# V1_0.net
KiCad netlist of a schematic drawn in Altium Designer
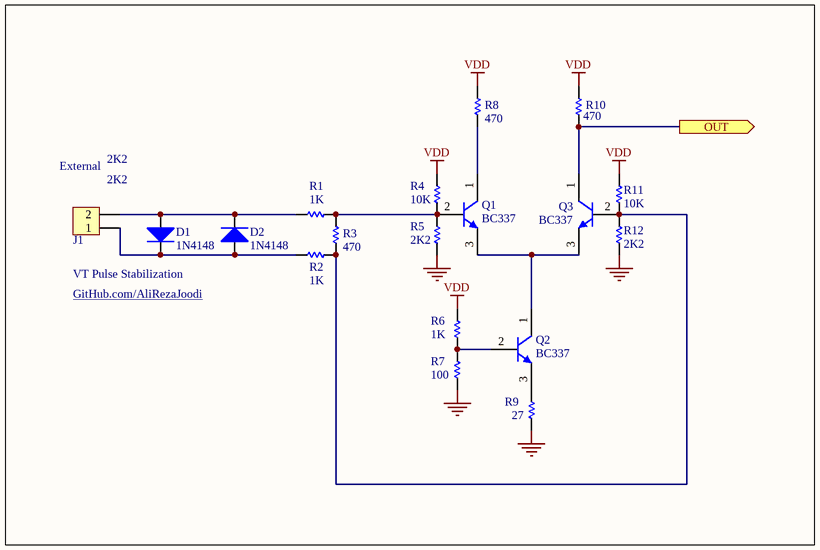
[diagram p0: V1.0.SchDoc]

(export (version "E")
  (design (tool "Eeschema 10.0.6"))
  (components
    (comp (ref "D1")
      (value "1N4148")
      (footprint "D_THD_AXIAL0.3_DO-35")
      (description "Diode,")
      (libsource (lib "Passive") (part "Diode"))
    )
    (comp (ref "D2")
      (value "1N4148")
      (footprint "D_THD_AXIAL0.3_DO-35")
      (description "Diode,")
      (libsource (lib "Passive") (part "Diode"))
    )
    (comp (ref "J1")
      (value "2PIN")
      (footprint "Connector_Phoenix_2PIN_MSTB")
      (description "Connector, Header, 2Pin")
      (libsource (lib "Connector") (part "Connector_Header_2Pin"))
    )
    (comp (ref "Q1")
      (value "BC337")
      (footprint "TO92_3Pin_Form3")
      (description "Transistor, BJT, NPN")
      (libsource (lib "Passive") (part "Transistor_BJT_NPN"))
    )
    (comp (ref "Q2")
      (value "BC337")
      (footprint "TO92_3Pin_Form3")
      (description "Transistor, BJT, NPN")
      (libsource (lib "Passive") (part "Transistor_BJT_NPN"))
    )
    (comp (ref "Q3")
      (value "BC337")
      (footprint "TO92_3Pin_Form3")
      (description "Transistor, BJT, NPN")
      (libsource (lib "Passive") (part "Transistor_BJT_NPN"))
    )
    (comp (ref "R1")
      (value "1K")
      (footprint "R_THD_AXIAL0.4(1/4W)")
      (description "Resistor,")
      (libsource (lib "Passive") (part "Resistor"))
    )
    (comp (ref "R2")
      (value "1K")
      (footprint "R_THD_AXIAL0.4(1/4W)")
      (description "Resistor,")
      (libsource (lib "Passive") (part "Resistor"))
    )
    (comp (ref "R3")
      (value "470")
      (footprint "R_THD_AXIAL0.4(1/4W)")
      (description "Resistor,")
      (libsource (lib "Passive") (part "Resistor"))
    )
    (comp (ref "R4")
      (value "10K")
      (footprint "R_THD_AXIAL0.4(1/4W)")
      (description "Resistor,")
      (libsource (lib "Passive") (part "Resistor"))
    )
    (comp (ref "R5")
      (value "2K2")
      (footprint "R_THD_AXIAL0.4(1/4W)")
      (description "Resistor,")
      (libsource (lib "Passive") (part "Resistor"))
    )
    (comp (ref "R6")
      (value "1K")
      (footprint "R_THD_AXIAL0.4(1/4W)")
      (description "Resistor,")
      (libsource (lib "Passive") (part "Resistor"))
    )
    (comp (ref "R7")
      (value "100")
      (footprint "R_THD_AXIAL0.4(1/4W)")
      (description "Resistor,")
      (libsource (lib "Passive") (part "Resistor"))
    )
    (comp (ref "R8")
      (value "470")
      (footprint "R_THD_AXIAL0.4(1/4W)")
      (description "Resistor,")
      (libsource (lib "Passive") (part "Resistor"))
    )
    (comp (ref "R9")
      (value "27")
      (footprint "R_THD_AXIAL0.4(1/4W)")
      (description "Resistor,")
      (libsource (lib "Passive") (part "Resistor"))
    )
    (comp (ref "R10")
      (value "470")
      (footprint "R_THD_AXIAL0.4(1/4W)")
      (description "Resistor,")
      (libsource (lib "Passive") (part "Resistor"))
    )
    (comp (ref "R11")
      (value "10K")
      (footprint "R_THD_AXIAL0.4(1/4W)")
      (description "Resistor,")
      (libsource (lib "Passive") (part "Resistor"))
    )
    (comp (ref "R12")
      (value "2K2")
      (footprint "R_THD_AXIAL0.4(1/4W)")
      (description "Resistor,")
      (libsource (lib "Passive") (part "Resistor"))
    )
  )
  (nets
    (net (code "1") (name "/OUT") (class "Default")
      (node (ref "Q3") (pin "1") (pinfunction "C_1") (pintype "passive"))
      (node (ref "R10") (pin "1") (pinfunction "1_1") (pintype "passive"))
    )
    (net (code "2") (name "GND") (class "Default")
      (node (ref "R12") (pin "1") (pinfunction "1_1") (pintype "passive"))
      (node (ref "R5") (pin "1") (pinfunction "1_1") (pintype "passive"))
      (node (ref "R7") (pin "1") (pinfunction "1_1") (pintype "passive"))
      (node (ref "R9") (pin "1") (pinfunction "1_1") (pintype "passive"))
    )
    (net (code "3") (name "Net-(D1-A)") (class "Default")
      (node (ref "D1") (pin "1") (pinfunction "A_1") (pintype "passive"))
      (node (ref "D2") (pin "2") (pinfunction "K_2") (pintype "passive"))
      (node (ref "J1") (pin "2") (pinfunction "2_2") (pintype "passive"))
      (node (ref "R1") (pin "2") (pinfunction "2_2") (pintype "passive"))
    )
    (net (code "4") (name "Net-(D1-K)") (class "Default")
      (node (ref "D1") (pin "2") (pinfunction "K_2") (pintype "passive"))
      (node (ref "D2") (pin "1") (pinfunction "A_1") (pintype "passive"))
      (node (ref "J1") (pin "1") (pinfunction "1_1") (pintype "passive"))
      (node (ref "R2") (pin "2") (pinfunction "2_2") (pintype "passive"))
    )
    (net (code "5") (name "Net-(Q1-B)") (class "Default")
      (node (ref "Q1") (pin "2") (pinfunction "B_2") (pintype "passive"))
      (node (ref "R1") (pin "1") (pinfunction "1_1") (pintype "passive"))
      (node (ref "R3") (pin "1") (pinfunction "1_1") (pintype "passive"))
      (node (ref "R4") (pin "1") (pinfunction "1_1") (pintype "passive"))
      (node (ref "R5") (pin "2") (pinfunction "2_2") (pintype "passive"))
    )
    (net (code "6") (name "Net-(Q1-C)") (class "Default")
      (node (ref "Q1") (pin "1") (pinfunction "C_1") (pintype "passive"))
      (node (ref "R8") (pin "1") (pinfunction "1_1") (pintype "passive"))
    )
    (net (code "7") (name "Net-(Q1-E)") (class "Default")
      (node (ref "Q1") (pin "3") (pinfunction "E_3") (pintype "passive"))
      (node (ref "Q2") (pin "1") (pinfunction "C_1") (pintype "passive"))
      (node (ref "Q3") (pin "3") (pinfunction "E_3") (pintype "passive"))
    )
    (net (code "8") (name "Net-(Q2-B)") (class "Default")
      (node (ref "Q2") (pin "2") (pinfunction "B_2") (pintype "passive"))
      (node (ref "R6") (pin "1") (pinfunction "1_1") (pintype "passive"))
      (node (ref "R7") (pin "2") (pinfunction "2_2") (pintype "passive"))
    )
    (net (code "9") (name "Net-(Q2-E)") (class "Default")
      (node (ref "Q2") (pin "3") (pinfunction "E_3") (pintype "passive"))
      (node (ref "R9") (pin "2") (pinfunction "2_2") (pintype "passive"))
    )
    (net (code "10") (name "Net-(Q3-B)") (class "Default")
      (node (ref "Q3") (pin "2") (pinfunction "B_2") (pintype "passive"))
      (node (ref "R11") (pin "1") (pinfunction "1_1") (pintype "passive"))
      (node (ref "R12") (pin "2") (pinfunction "2_2") (pintype "passive"))
      (node (ref "R2") (pin "1") (pinfunction "1_1") (pintype "passive"))
      (node (ref "R3") (pin "2") (pinfunction "2_2") (pintype "passive"))
    )
    (net (code "11") (name "VDD") (class "Default")
      (node (ref "R10") (pin "2") (pinfunction "2_2") (pintype "passive"))
      (node (ref "R11") (pin "2") (pinfunction "2_2") (pintype "passive"))
      (node (ref "R4") (pin "2") (pinfunction "2_2") (pintype "passive"))
      (node (ref "R6") (pin "2") (pinfunction "2_2") (pintype "passive"))
      (node (ref "R8") (pin "2") (pinfunction "2_2") (pintype "passive"))
    )
  )
)
